# Led_Driver_Flashlight.net
KiCad netlist of a schematic drawn in EasyEDA
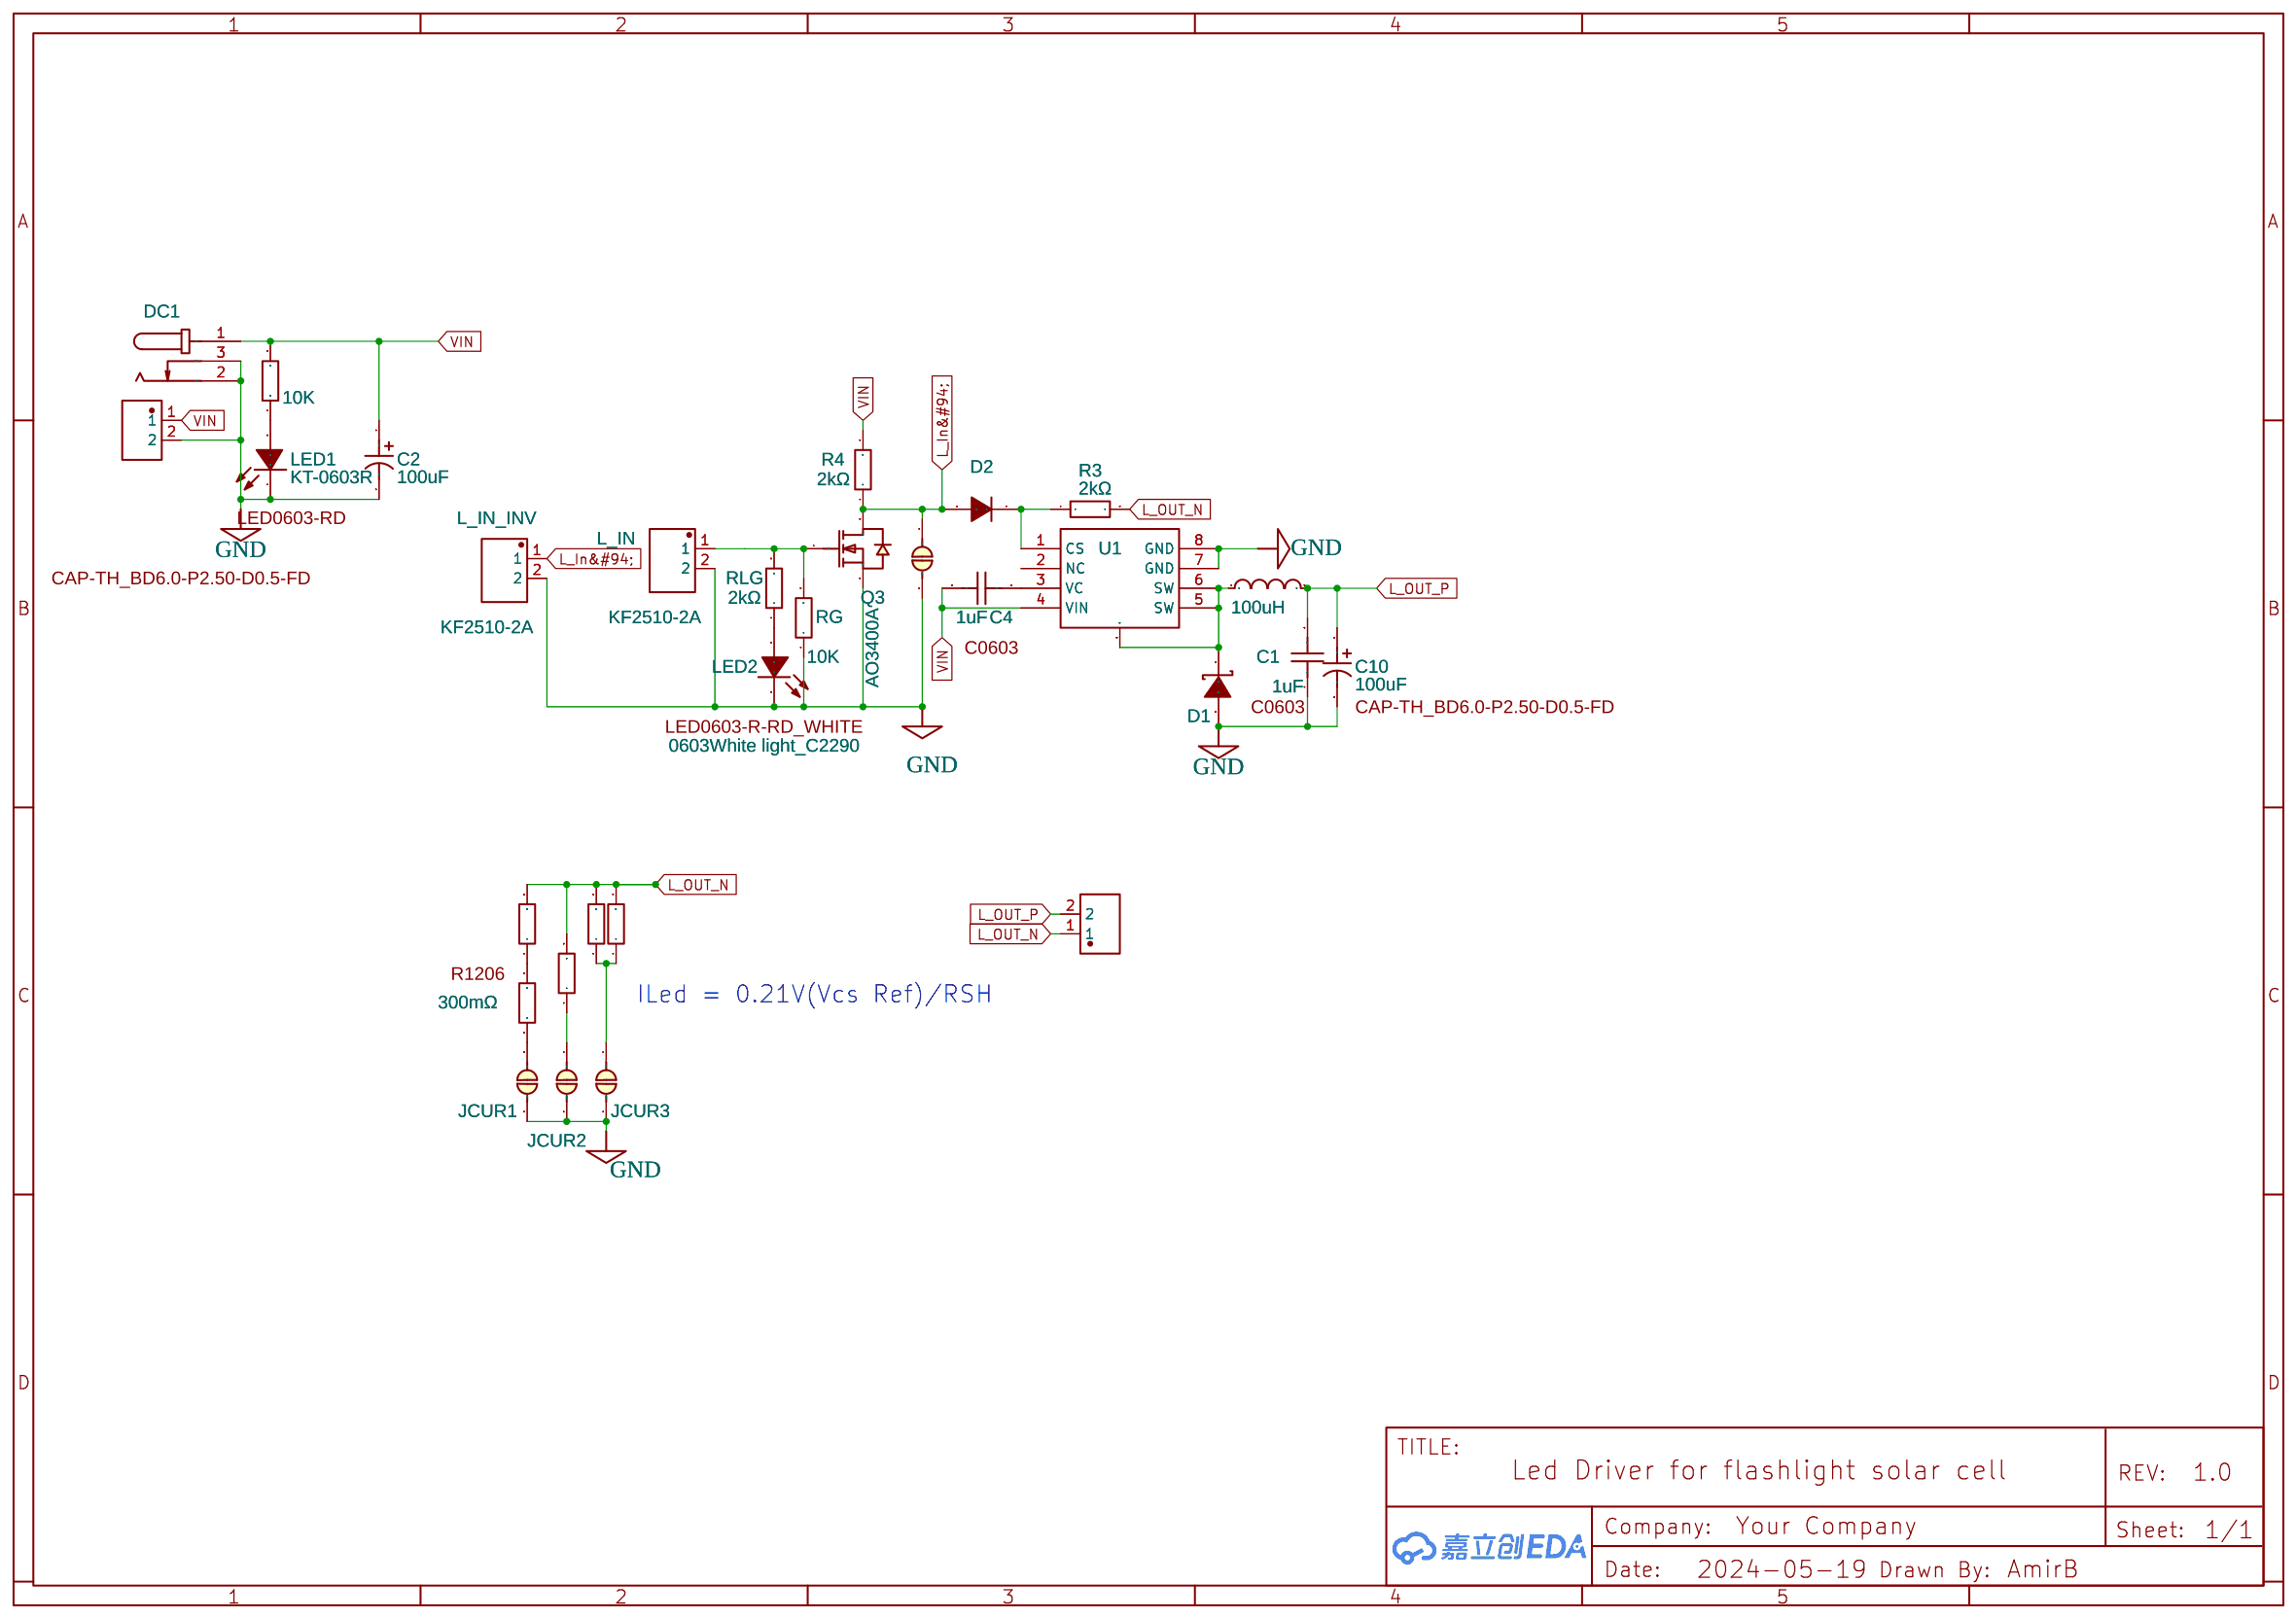
[diagram p0: schematic sheet]

(export (version "E")
  (design (tool "Eeschema 10.0.6"))
  (components
    (comp (ref "C1")
      (value "1uF")
      (fields
        (field (name "Manufacturer Part") "CL10A105KB8NNNC")
        (field (name "Manufacturer") "SAMSUNG(三星)")
      )
      (libsource (lib "") (part "CL10A105KB8NNNC"))
    )
    (comp (ref "C2")
      (value "100uF")
      (fields (field (name "Manufacturer Part") "03EC0673") (field (name "Manufacturer") "KNSCHA(科尼盛)"))
      (libsource (lib "") (part "03EC0673"))
    )
    (comp (ref "C4")
      (value "1uF")
      (fields
        (field (name "Manufacturer Part") "CL10A105KB8NNNC")
        (field (name "Manufacturer") "SAMSUNG(三星)")
      )
      (libsource (lib "") (part "CL10A105KB8NNNC_1"))
    )
    (comp (ref "C10")
      (value "100uF")
      (fields (field (name "Manufacturer Part") "03EC0673") (field (name "Manufacturer") "KNSCHA(科尼盛)"))
      (libsource (lib "") (part "03EC0673_1"))
    )
    (comp (ref "CNVIN")
      (value "MX126-5.0-GN01-02P-CU-S-A")
      (fields
        (field (name "Manufacturer Part") "MX126-5.0-GN01-02P-Cu-S-A")
        (field (name "Manufacturer") "MAX(迈旭)")
      )
      (libsource (lib "") (part "MX126-5.0-GN01-02P-CU-S-A"))
    )
    (comp (ref "CN_L")
      (value "MX126-5.0-GN01-02P-CU-S-A")
      (fields
        (field (name "Manufacturer Part") "MX126-5.0-GN01-02P-Cu-S-A")
        (field (name "Manufacturer") "MAX(迈旭)")
      )
      (libsource (lib "") (part "MX126-5.0-GN01-02P-CU-S-A_1"))
    )
    (comp (ref "D1")
      (value "B540C-13-F")
      (fields (field (name "Manufacturer") "DIODES(美台)"))
      (libsource (lib "") (part "B540C-13-F"))
    )
    (comp (ref "D2")
      (value "1N4148WS T4")
      (fields (field (name "Manufacturer Part") "1N4148WS") (field (name "Manufacturer") "CJ(江苏长电/长晶)"))
      (libsource (lib "") (part "1N4148WS T4"))
    )
    (comp (ref "DC1")
      (value "DC005-2.0MM")
      (fields (field (name "Manufacturer Part") "DC005-T20") (field (name "Manufacturer") "SOFNG(硕方)"))
      (libsource (lib "") (part "DC005-2.0MM"))
    )
    (comp (ref "JCUR1") (value "JUMPER-VLDO") (libsource (lib "") (part "JUMPER-SMT_2")))
    (comp (ref "JCUR2") (value "JUMPER-VLDO") (libsource (lib "") (part "JUMPER-SMT_2")))
    (comp (ref "JCUR3") (value "JUMPER-VLDO") (libsource (lib "") (part "JUMPER-SMT_2")))
    (comp (ref "JON") (value "JUMPER-VLDO") (libsource (lib "") (part "JUMPER-SMT_2_1")))
    (comp (ref "L1")
      (value "100uH")
      (fields
        (field (name "Manufacturer Part") "MWSA1206S-101MT")
        (field (name "Manufacturer") "Sunlord(顺络)")
      )
      (libsource (lib "") (part "MWSA1206S-101MT"))
    )
    (comp (ref "LED1")
      (value "KT-0603R")
      (fields (field (name "Manufacturer") "KENTO"))
      (libsource (lib "") (part "KT-0603R"))
    )
    (comp (ref "LED2")
      (value "0603White light_C2290")
      (fields (field (name "Manufacturer Part") "KT-0603白灯") (field (name "Manufacturer") "KENTO"))
      (libsource (lib "") (part "0603White light_C2290"))
    )
    (comp (ref "L_IN")
      (value "KF2510-2A")
      (fields (field (name "BOM_Supplier Part") "C27543"))
      (libsource (lib "") (part "KF2510-2A_1"))
    )
    (comp (ref "L_IN_INV")
      (value "KF2510-2A")
      (fields (field (name "BOM_Supplier Part") "C27543"))
      (libsource (lib "") (part "KF2510-2A"))
    )
    (comp (ref "Q3")
      (value "AO3400A")
      (fields (field (name "Manufacturer") "AOS"))
      (libsource (lib "") (part "AO3400A"))
    )
    (comp (ref "R3")
      (value "2kΩ")
      (fields
        (field (name "Manufacturer Part") "0603WAF2001T5E")
        (field (name "Manufacturer") "UNI-ROYAL(厚声)")
      )
      (libsource (lib "") (part "0603WAF2001T5E"))
    )
    (comp (ref "R4")
      (value "2kΩ")
      (fields
        (field (name "Manufacturer Part") "0603WAF2001T5E")
        (field (name "Manufacturer") "UNI-ROYAL(厚声)")
      )
      (libsource (lib "") (part "0603WAF2001T5E_2"))
    )
    (comp (ref "RG")
      (value "10K")
      (fields
        (field (name "BOM_Manufacturer Part") "0603WAF1002T5E")
        (field (name "BOM_Supplier Part") "C25804")
      )
      (libsource (lib "") (part "0603WAF1001T5E"))
    )
    (comp (ref "RL1")
      (value "10K")
      (fields
        (field (name "BOM_Manufacturer Part") "0603WAF1002T5E")
        (field (name "BOM_Supplier Part") "C25804")
      )
      (libsource (lib "") (part "0603WAF1001T5E_1"))
    )
    (comp (ref "RLG")
      (value "2kΩ")
      (fields
        (field (name "Manufacturer Part") "0603WAF2001T5E")
        (field (name "Manufacturer") "UNI-ROYAL(厚声)")
      )
      (libsource (lib "") (part "0603WAF2001T5E_1"))
    )
    (comp (ref "RS1")
      (value "300mΩ")
      (fields
        (field (name "Manufacturer Part") "1206W4F300LT5E")
        (field (name "Manufacturer") "UNI-ROYAL(厚声)")
      )
      (libsource (lib "") (part "1206W4F300LT5E"))
    )
    (comp (ref "RS2")
      (value "300mΩ")
      (fields
        (field (name "Manufacturer Part") "1206W4F300LT5E")
        (field (name "Manufacturer") "UNI-ROYAL(厚声)")
      )
      (libsource (lib "") (part "1206W4F300LT5E_1"))
    )
    (comp (ref "RS3")
      (value "300mΩ")
      (fields
        (field (name "Manufacturer Part") "1206W4F300LT5E")
        (field (name "Manufacturer") "UNI-ROYAL(厚声)")
      )
      (libsource (lib "") (part "1206W4F300LT5E"))
    )
    (comp (ref "RS4")
      (value "300mΩ")
      (fields
        (field (name "Manufacturer Part") "1206W4F300LT5E")
        (field (name "Manufacturer") "UNI-ROYAL(厚声)")
      )
      (libsource (lib "") (part "1206W4F300LT5E"))
    )
    (comp (ref "RS5")
      (value "300mΩ")
      (fields
        (field (name "Manufacturer Part") "1206W4F300LT5E")
        (field (name "Manufacturer") "UNI-ROYAL(厚声)")
      )
      (libsource (lib "") (part "1206W4F300LT5E"))
    )
    (comp (ref "U1")
      (value "-")
      (fields (field (name "Manufacturer Part") "XL3001E1") (field (name "Manufacturer") "XLSEMI(芯龙)"))
      (libsource (lib "") (part "XL3001E1"))
    )
  )
  (nets
    (net (code "1") (name "GND") (class "Default")
      (node (ref "C1") (pin "1") (pinfunction "1_1") (pintype "unspecified"))
      (node (ref "C10") (pin "2") (pinfunction "2_2") (pintype "input"))
      (node (ref "C2") (pin "2") (pinfunction "2_2") (pintype "input"))
      (node (ref "CNVIN") (pin "2") (pinfunction "2_2") (pintype "unspecified"))
      (node (ref "D1") (pin "2") (pinfunction "A_2") (pintype "unspecified"))
      (node (ref "DC1") (pin "2") (pinfunction "2_2") (pintype "unspecified"))
      (node (ref "DC1") (pin "3") (pinfunction "3_3") (pintype "unspecified"))
      (node (ref "JCUR1") (pin "2") (pinfunction "2_2") (pintype "bidirectional"))
      (node (ref "JCUR2") (pin "2") (pinfunction "2_2") (pintype "bidirectional"))
      (node (ref "JCUR3") (pin "2") (pinfunction "2_2") (pintype "bidirectional"))
      (node (ref "JON") (pin "2") (pinfunction "2_2") (pintype "bidirectional"))
      (node (ref "LED1") (pin "1") (pinfunction "K_1") (pintype "unspecified"))
      (node (ref "LED2") (pin "2") (pinfunction "K_2") (pintype "unspecified"))
      (node (ref "L_IN") (pin "2") (pinfunction "2_2") (pintype "unspecified"))
      (node (ref "L_IN_INV") (pin "2") (pinfunction "2_2") (pintype "unspecified"))
      (node (ref "Q3") (pin "2") (pinfunction "S_2") (pintype "unspecified"))
      (node (ref "RG") (pin "1") (pinfunction "1_1") (pintype "input"))
      (node (ref "U1") (pin "7") (pinfunction "GND_7") (pintype "unspecified"))
      (node (ref "U1") (pin "8") (pinfunction "GND_8") (pintype "unspecified"))
    )
    (net (code "2") (name "L_In&#94;") (class "Default")
      (node (ref "D2") (pin "2") (pinfunction "A_2") (pintype "unspecified"))
      (node (ref "JON") (pin "1") (pinfunction "1_1") (pintype "bidirectional"))
      (node (ref "L_IN_INV") (pin "1") (pinfunction "1_1") (pintype "unspecified"))
      (node (ref "Q3") (pin "3") (pinfunction "D_3") (pintype "unspecified"))
      (node (ref "R4") (pin "1") (pinfunction "1_1") (pintype "input"))
    )
    (net (code "3") (name "L_OUT_N") (class "Default")
      (node (ref "CN_L") (pin "1") (pinfunction "1_1") (pintype "unspecified"))
      (node (ref "R3") (pin "2") (pinfunction "2_2") (pintype "input"))
      (node (ref "RS1") (pin "2") (pinfunction "2_2") (pintype "input"))
      (node (ref "RS3") (pin "2") (pinfunction "2_2") (pintype "input"))
      (node (ref "RS4") (pin "2") (pinfunction "2_2") (pintype "input"))
      (node (ref "RS5") (pin "2") (pinfunction "2_2") (pintype "input"))
    )
    (net (code "4") (name "L_OUT_P") (class "Default")
      (node (ref "C1") (pin "2") (pinfunction "2_2") (pintype "unspecified"))
      (node (ref "C10") (pin "1") (pinfunction "1_1") (pintype "input"))
      (node (ref "CN_L") (pin "2") (pinfunction "2_2") (pintype "unspecified"))
      (node (ref "L1") (pin "2") (pinfunction "2_2") (pintype "unspecified"))
    )
    (net (code "5") (name "Net-(D1-K)") (class "Default")
      (node (ref "D1") (pin "1") (pinfunction "K_1") (pintype "unspecified"))
      (node (ref "L1") (pin "1") (pinfunction "1_1") (pintype "unspecified"))
      (node (ref "U1") (pin "5") (pinfunction "SW_5") (pintype "unspecified"))
      (node (ref "U1") (pin "6") (pinfunction "SW_6") (pintype "unspecified"))
      (node (ref "U1") (pin "9") (pinfunction "9_9") (pintype "unspecified"))
    )
    (net (code "6") (name "Net-(D2-K)") (class "Default")
      (node (ref "D2") (pin "1") (pinfunction "K_1") (pintype "unspecified"))
      (node (ref "R3") (pin "1") (pinfunction "1_1") (pintype "input"))
      (node (ref "U1") (pin "1") (pinfunction "CS_1") (pintype "unspecified"))
    )
    (net (code "7") (name "Net-(JCUR1-Pad1)") (class "Default")
      (node (ref "JCUR1") (pin "1") (pinfunction "1_1") (pintype "bidirectional"))
      (node (ref "RS2") (pin "1") (pinfunction "1_1") (pintype "input"))
    )
    (net (code "8") (name "Net-(JCUR2-Pad1)") (class "Default")
      (node (ref "JCUR2") (pin "1") (pinfunction "1_1") (pintype "bidirectional"))
      (node (ref "RS3") (pin "1") (pinfunction "1_1") (pintype "input"))
    )
    (net (code "9") (name "Net-(JCUR3-Pad1)") (class "Default")
      (node (ref "JCUR3") (pin "1") (pinfunction "1_1") (pintype "bidirectional"))
      (node (ref "RS4") (pin "1") (pinfunction "1_1") (pintype "input"))
      (node (ref "RS5") (pin "1") (pinfunction "1_1") (pintype "input"))
    )
    (net (code "10") (name "Net-(LED1-A)") (class "Default")
      (node (ref "LED1") (pin "2") (pinfunction "A_2") (pintype "unspecified"))
      (node (ref "RL1") (pin "1") (pinfunction "1_1") (pintype "input"))
    )
    (net (code "11") (name "Net-(LED2-A)") (class "Default")
      (node (ref "LED2") (pin "1") (pinfunction "A_1") (pintype "unspecified"))
      (node (ref "RLG") (pin "1") (pinfunction "1_1") (pintype "input"))
    )
    (net (code "12") (name "Net-(Q3-G)") (class "Default")
      (node (ref "L_IN") (pin "1") (pinfunction "1_1") (pintype "unspecified"))
      (node (ref "Q3") (pin "1") (pinfunction "G_1") (pintype "unspecified"))
      (node (ref "RG") (pin "2") (pinfunction "2_2") (pintype "input"))
      (node (ref "RLG") (pin "2") (pinfunction "2_2") (pintype "input"))
    )
    (net (code "13") (name "Net-(RS1-Pad1)") (class "Default")
      (node (ref "RS1") (pin "1") (pinfunction "1_1") (pintype "input"))
      (node (ref "RS2") (pin "2") (pinfunction "2_2") (pintype "input"))
    )
    (net (code "14") (name "Net-(U1-VC)") (class "Default")
      (node (ref "C4") (pin "2") (pinfunction "2_2") (pintype "unspecified"))
      (node (ref "U1") (pin "3") (pinfunction "VC_3") (pintype "unspecified"))
    )
    (net (code "15") (name "VIN") (class "Default")
      (node (ref "C2") (pin "1") (pinfunction "1_1") (pintype "input"))
      (node (ref "C4") (pin "1") (pinfunction "1_1") (pintype "unspecified"))
      (node (ref "CNVIN") (pin "1") (pinfunction "1_1") (pintype "unspecified"))
      (node (ref "DC1") (pin "1") (pinfunction "1_1") (pintype "unspecified"))
      (node (ref "R4") (pin "2") (pinfunction "2_2") (pintype "input"))
      (node (ref "RL1") (pin "2") (pinfunction "2_2") (pintype "input"))
      (node (ref "U1") (pin "4") (pinfunction "VIN_4") (pintype "unspecified"))
    )
    (net (code "16") (name "unconnected-(U1-NC-Pad2)") (class "Default")
      (node (ref "U1") (pin "2") (pinfunction "NC_2") (pintype "unspecified"))
    )
  )
)
